# Esq.net
KiCad netlist of a schematic drawn in Altium Designer
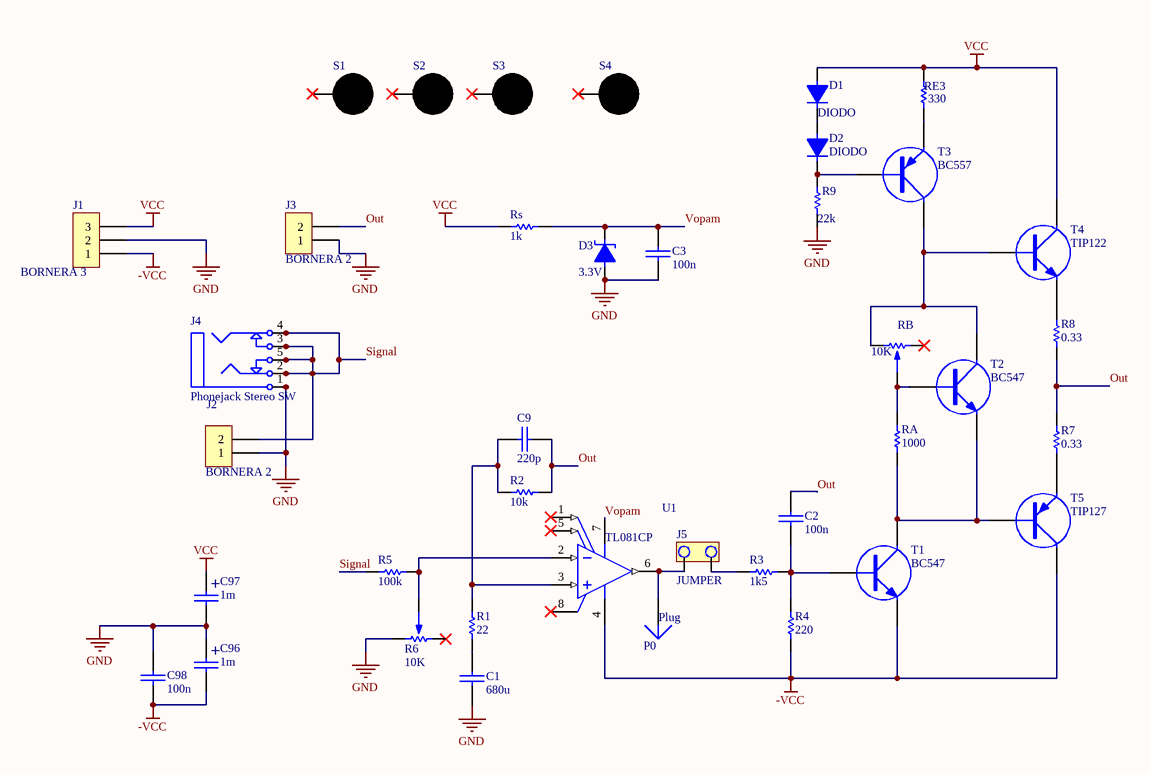
[diagram p0: Esq.SchDoc]

(export (version "E")
  (design (tool "Eeschema 10.0.6"))
  (components
    (comp (ref "C1") (value "680u") (footprint "CAP200") (libsource (lib "LIB PIO IX") (part "CAP")))
    (comp (ref "C2") (value "100n") (footprint "CAP200") (libsource (lib "LIB PIO IX") (part "CAP")))
    (comp (ref "C3") (value "100n") (footprint "CAP200") (libsource (lib "LIB PIO IX") (part "CAP")))
    (comp (ref "C9") (value "220p") (footprint "CAP200") (libsource (lib "LIB PIO IX") (part "CAP")))
    (comp (ref "C96") (value "1m") (footprint "CAP200RP2") (libsource (lib "LIB PIO IX") (part "CAPPOL")))
    (comp (ref "C97") (value "1m") (footprint "CAP200RP2") (libsource (lib "LIB PIO IX") (part "CAPPOL")))
    (comp (ref "C98") (value "100n") (footprint "CAP200") (libsource (lib "LIB PIO IX") (part "CAP")))
    (comp (ref "D1") (value "DIODO") (footprint "DO41") (libsource (lib "LIB PIO IX") (part "DIODO")))
    (comp (ref "D2") (value "DIODO") (footprint "DO41") (libsource (lib "LIB PIO IX") (part "DIODO")))
    (comp (ref "D3") (value "3.3V") (footprint "DO41") (libsource (lib "LIB PIO IX") (part "DIODO ZENER")))
    (comp (ref "J1")
      (value "BORNERA 3")
      (footprint "BORNERA3")
      (libsource (lib "LIB PIO IX") (part "BORNERA 3"))
    )
    (comp (ref "J2")
      (value "BORNERA 2")
      (footprint "BORNERA2")
      (libsource (lib "LIB PIO IX") (part "BORNERA 2"))
    )
    (comp (ref "J3")
      (value "BORNERA 2")
      (footprint "BORNERA2")
      (libsource (lib "LIB PIO IX") (part "BORNERA 2"))
    )
    (comp (ref "J4")
      (value "Phonejack Stereo SW")
      (footprint "ST-3150-5N")
      (description "3-Conductor Jack with 2 break contacts (normals) and 2 auxiliary make contacts")
      (fields (field (name "PUBLISHER") "Altium Limited"))
      (libsource (lib "Miscellaneous Connectors") (part "Phonejack Stereo SW"))
    )
    (comp (ref "J5") (value "JUMPER") (footprint "JUMPER2") (libsource (lib "LIB PIO IX") (part "JUMPER")))
    (comp (ref "P0")
      (value "Plug")
      (footprint "PIN1")
      (fields (field (name "PUBLISHER") "Altium Limited"))
      (libsource (lib "Miscellaneous Connectors") (part "Plug"))
    )
    (comp (ref "R1") (value "22") (footprint "RES400") (libsource (lib "LIB PIO IX") (part "RES")))
    (comp (ref "R2") (value "10k") (footprint "RES400") (libsource (lib "LIB PIO IX") (part "RES")))
    (comp (ref "R3") (value "1k5") (footprint "RES400") (libsource (lib "LIB PIO IX") (part "RES")))
    (comp (ref "R4") (value "220") (footprint "RES400") (libsource (lib "LIB PIO IX") (part "RES")))
    (comp (ref "R5") (value "100k") (footprint "RES400") (libsource (lib "LIB PIO IX") (part "RES")))
    (comp (ref "R6") (value "10K") (footprint "PRESET V") (libsource (lib "LIB PIO IX") (part "PRESET")))
    (comp (ref "R7") (value "0.33") (footprint "RES600") (libsource (lib "LIB PIO IX") (part "RES")))
    (comp (ref "R8") (value "0.33") (footprint "RES600") (libsource (lib "LIB PIO IX") (part "RES")))
    (comp (ref "R9") (value "22k") (footprint "RES400") (libsource (lib "LIB PIO IX") (part "RES")))
    (comp (ref "RA") (value "1000") (footprint "RES400") (libsource (lib "LIB PIO IX") (part "RES")))
    (comp (ref "RB") (value "10K") (footprint "PRESET V") (libsource (lib "LIB PIO IX") (part "PRESET")))
    (comp (ref "RE3") (value "330") (footprint "RES400") (libsource (lib "LIB PIO IX") (part "RES")))
    (comp (ref "Rs") (value "1k") (footprint "RES600") (libsource (lib "LIB PIO IX") (part "RES")))
    (comp (ref "S1")
      (value "~")
      (footprint "SUJECION (5.00MM - 3.50MM)")
      (libsource (lib "LIB2013") (part "SUJECION"))
    )
    (comp (ref "S2")
      (value "~")
      (footprint "SUJECION (5.00MM - 3.50MM)")
      (libsource (lib "LIB2013") (part "SUJECION"))
    )
    (comp (ref "S3")
      (value "~")
      (footprint "SUJECION (5.00MM - 3.50MM)")
      (libsource (lib "LIB2013") (part "SUJECION"))
    )
    (comp (ref "S4")
      (value "~")
      (footprint "SUJECION (5.00MM - 3.50MM)")
      (libsource (lib "LIB2013") (part "SUJECION"))
    )
    (comp (ref "T1")
      (value "BC547")
      (footprint "TO92")
      (libsource (lib "LIB PIO IX") (part "TRANSISTOR NPN"))
    )
    (comp (ref "T2")
      (value "BC547")
      (footprint "TO92")
      (libsource (lib "LIB PIO IX") (part "TRANSISTOR NPN"))
    )
    (comp (ref "T3")
      (value "BC557")
      (footprint "TO92")
      (libsource (lib "LIB PIO IX") (part "TRANSISTOR PNP"))
    )
    (comp (ref "T4")
      (value "TIP122")
      (footprint "TO-220 V")
      (libsource (lib "LIB PIO IX") (part "TRANSISTOR NPN"))
    )
    (comp (ref "T5")
      (value "TIP127")
      (footprint "TO-220 V")
      (libsource (lib "LIB PIO IX") (part "TRANSISTOR PNP"))
    )
    (comp (ref "U1")
      (value "TL081CP")
      (footprint "P0008A")
      (description "JFET-Input Operational Amplifier, 7 to 36 V, 0 to 70 degC, 8-pin DIP (P8), Pb-Free (RoHS)")
      (fields (field (name "MANUFACTURER") "Texas Instruments"))
      (libsource (lib "Altium Content Vault") (part "TI-AMP-S5-2-8"))
    )
  )
  (nets
    (net (code "1") (name "-VCC") (class "Default")
      (node (ref "C96") (pin "2") (pinfunction "2_2") (pintype "passive"))
      (node (ref "C98") (pin "1") (pinfunction "1_1") (pintype "passive"))
      (node (ref "J1") (pin "1") (pinfunction "1_1") (pintype "passive"))
      (node (ref "R4") (pin "1") (pinfunction "1_1") (pintype "passive"))
      (node (ref "T1") (pin "3") (pinfunction "E_3") (pintype "passive"))
      (node (ref "T5") (pin "2") (pinfunction "C_2") (pintype "passive"))
      (node (ref "U1") (pin "4") (pinfunction "VCC-_4") (pintype "power_in"))
    )
    (net (code "2") (name "/Out") (class "Default")
      (node (ref "C2") (pin "1") (pinfunction "1_1") (pintype "passive"))
      (node (ref "C9") (pin "2") (pinfunction "2_2") (pintype "passive"))
      (node (ref "J3") (pin "2") (pinfunction "2_2") (pintype "passive"))
      (node (ref "R2") (pin "2") (pinfunction "2_2") (pintype "passive"))
      (node (ref "R7") (pin "2") (pinfunction "2_2") (pintype "passive"))
      (node (ref "R8") (pin "1") (pinfunction "1_1") (pintype "passive"))
    )
    (net (code "3") (name "/Signal") (class "Default")
      (node (ref "J2") (pin "2") (pinfunction "2_2") (pintype "passive"))
      (node (ref "J4") (pin "2") (pinfunction "2_2") (pintype "passive"))
      (node (ref "J4") (pin "2A") (pinfunction "2A_2A") (pintype "passive"))
      (node (ref "J4") (pin "2B") (pinfunction "2B_2B") (pintype "passive"))
      (node (ref "J4") (pin "3") (pinfunction "3_3") (pintype "passive"))
      (node (ref "J4") (pin "3A") (pinfunction "3A_3A") (pintype "passive"))
      (node (ref "J4") (pin "3B") (pinfunction "3B_3B") (pintype "passive"))
      (node (ref "J4") (pin "4") (pinfunction "4_4") (pintype "passive"))
      (node (ref "J4") (pin "4A") (pinfunction "4A_4A") (pintype "passive"))
      (node (ref "J4") (pin "4B") (pinfunction "4B_4B") (pintype "passive"))
      (node (ref "J4") (pin "5") (pinfunction "5_5") (pintype "passive"))
      (node (ref "J4") (pin "5A") (pinfunction "5A_5A") (pintype "passive"))
      (node (ref "J4") (pin "5B") (pinfunction "5B_5B") (pintype "passive"))
      (node (ref "R5") (pin "2") (pinfunction "2_2") (pintype "passive"))
    )
    (net (code "4") (name "/Vopam") (class "Default")
      (node (ref "C3") (pin "2") (pinfunction "2_2") (pintype "passive"))
      (node (ref "D3") (pin "2") (pinfunction "2_2") (pintype "passive"))
      (node (ref "Rs") (pin "2") (pinfunction "2_2") (pintype "passive"))
      (node (ref "U1") (pin "7") (pinfunction "VCC+_7") (pintype "power_in"))
    )
    (net (code "5") (name "GND") (class "Default")
      (node (ref "C1") (pin "2") (pinfunction "2_2") (pintype "passive"))
      (node (ref "C3") (pin "1") (pinfunction "1_1") (pintype "passive"))
      (node (ref "C96") (pin "1") (pinfunction "1_1") (pintype "passive"))
      (node (ref "C97") (pin "2") (pinfunction "2_2") (pintype "passive"))
      (node (ref "C98") (pin "2") (pinfunction "2_2") (pintype "passive"))
      (node (ref "D3") (pin "1") (pinfunction "1_1") (pintype "passive"))
      (node (ref "J1") (pin "2") (pinfunction "2_2") (pintype "passive"))
      (node (ref "J2") (pin "1") (pinfunction "1_1") (pintype "passive"))
      (node (ref "J3") (pin "1") (pinfunction "1_1") (pintype "passive"))
      (node (ref "J4") (pin "1") (pinfunction "1_1") (pintype "passive"))
      (node (ref "J4") (pin "1A") (pinfunction "1A_1A") (pintype "passive"))
      (node (ref "J4") (pin "1B") (pinfunction "1B_1B") (pintype "passive"))
      (node (ref "R6") (pin "1") (pinfunction "1_1") (pintype "passive"))
      (node (ref "R9") (pin "1") (pinfunction "1_1") (pintype "passive"))
    )
    (net (code "6") (name "Net-(C1-Pad1)") (class "Default")
      (node (ref "C1") (pin "1") (pinfunction "1_1") (pintype "passive"))
      (node (ref "R1") (pin "1") (pinfunction "1_1") (pintype "passive"))
    )
    (net (code "7") (name "Net-(D1-Pad2)") (class "Default")
      (node (ref "D1") (pin "2") (pinfunction "2_2") (pintype "passive"))
      (node (ref "D2") (pin "1") (pinfunction "1_1") (pintype "passive"))
    )
    (net (code "8") (name "Net-(J5-Pad1)") (class "Default")
      (node (ref "J5") (pin "1") (pinfunction "1_1") (pintype "passive"))
      (node (ref "R3") (pin "1") (pinfunction "1_1") (pintype "passive"))
    )
    (net (code "9") (name "Net-(T1-B)") (class "Default")
      (node (ref "C2") (pin "2") (pinfunction "2_2") (pintype "passive"))
      (node (ref "R3") (pin "2") (pinfunction "2_2") (pintype "passive"))
      (node (ref "R4") (pin "2") (pinfunction "2_2") (pintype "passive"))
      (node (ref "T1") (pin "1") (pinfunction "B_1") (pintype "passive"))
    )
    (net (code "10") (name "Net-(T1-C)") (class "Default")
      (node (ref "RA") (pin "1") (pinfunction "1_1") (pintype "passive"))
      (node (ref "T1") (pin "2") (pinfunction "C_2") (pintype "passive"))
      (node (ref "T2") (pin "3") (pinfunction "E_3") (pintype "passive"))
      (node (ref "T5") (pin "1") (pinfunction "B_1") (pintype "passive"))
    )
    (net (code "11") (name "Net-(T2-B)") (class "Default")
      (node (ref "RA") (pin "2") (pinfunction "2_2") (pintype "passive"))
      (node (ref "RB") (pin "2") (pinfunction "2_2") (pintype "passive"))
      (node (ref "T2") (pin "1") (pinfunction "B_1") (pintype "passive"))
    )
    (net (code "12") (name "Net-(T2-C)") (class "Default")
      (node (ref "RB") (pin "3") (pinfunction "3_3") (pintype "passive"))
      (node (ref "T2") (pin "2") (pinfunction "C_2") (pintype "passive"))
      (node (ref "T3") (pin "2") (pinfunction "C_2") (pintype "passive"))
      (node (ref "T4") (pin "1") (pinfunction "B_1") (pintype "passive"))
    )
    (net (code "13") (name "Net-(T3-B)") (class "Default")
      (node (ref "D2") (pin "2") (pinfunction "2_2") (pintype "passive"))
      (node (ref "R9") (pin "2") (pinfunction "2_2") (pintype "passive"))
      (node (ref "T3") (pin "1") (pinfunction "B_1") (pintype "passive"))
    )
    (net (code "14") (name "Net-(T3-E)") (class "Default")
      (node (ref "RE3") (pin "1") (pinfunction "1_1") (pintype "passive"))
      (node (ref "T3") (pin "3") (pinfunction "E_3") (pintype "passive"))
    )
    (net (code "15") (name "Net-(T4-E)") (class "Default")
      (node (ref "R8") (pin "2") (pinfunction "2_2") (pintype "passive"))
      (node (ref "T4") (pin "3") (pinfunction "E_3") (pintype "passive"))
    )
    (net (code "16") (name "Net-(T5-E)") (class "Default")
      (node (ref "R7") (pin "1") (pinfunction "1_1") (pintype "passive"))
      (node (ref "T5") (pin "3") (pinfunction "E_3") (pintype "passive"))
    )
    (net (code "17") (name "Net-(U1-IN+)") (class "Default")
      (node (ref "C9") (pin "1") (pinfunction "1_1") (pintype "passive"))
      (node (ref "R1") (pin "2") (pinfunction "2_2") (pintype "passive"))
      (node (ref "R2") (pin "1") (pinfunction "1_1") (pintype "passive"))
      (node (ref "U1") (pin "3") (pinfunction "IN+_3") (pintype "input"))
    )
    (net (code "18") (name "Net-(U1-IN-)") (class "Default")
      (node (ref "R5") (pin "1") (pinfunction "1_1") (pintype "passive"))
      (node (ref "R6") (pin "2") (pinfunction "2_2") (pintype "passive"))
      (node (ref "U1") (pin "2") (pinfunction "IN-_2") (pintype "input"))
    )
    (net (code "19") (name "Net-(U1-OUT)") (class "Default")
      (node (ref "J5") (pin "2") (pinfunction "2_2") (pintype "passive"))
      (node (ref "P0") (pin "1") (pinfunction "1_1") (pintype "passive"))
      (node (ref "U1") (pin "6") (pinfunction "OUT_6") (pintype "output"))
    )
    (net (code "20") (name "VCC") (class "Default")
      (node (ref "C97") (pin "1") (pinfunction "1_1") (pintype "passive"))
      (node (ref "D1") (pin "1") (pinfunction "1_1") (pintype "passive"))
      (node (ref "J1") (pin "3") (pinfunction "3_3") (pintype "passive"))
      (node (ref "RE3") (pin "2") (pinfunction "2_2") (pintype "passive"))
      (node (ref "Rs") (pin "1") (pinfunction "1_1") (pintype "passive"))
      (node (ref "T4") (pin "2") (pinfunction "C_2") (pintype "passive"))
    )
    (net (code "21") (name "unconnected-(R6-Pad3)") (class "Default")
      (node (ref "R6") (pin "3") (pinfunction "3_3") (pintype "passive+no_connect"))
    )
    (net (code "22") (name "unconnected-(RB-Pad1)") (class "Default")
      (node (ref "RB") (pin "1") (pinfunction "1_1") (pintype "passive+no_connect"))
    )
    (net (code "23") (name "unconnected-(S1-Pad1)") (class "Default")
      (node (ref "S1") (pin "1") (pinfunction "1_1") (pintype "passive+no_connect"))
    )
    (net (code "24") (name "unconnected-(S2-Pad1)") (class "Default")
      (node (ref "S2") (pin "1") (pinfunction "1_1") (pintype "passive+no_connect"))
    )
    (net (code "25") (name "unconnected-(S3-Pad1)") (class "Default")
      (node (ref "S3") (pin "1") (pinfunction "1_1") (pintype "passive+no_connect"))
    )
    (net (code "26") (name "unconnected-(S4-Pad1)") (class "Default")
      (node (ref "S4") (pin "1") (pinfunction "1_1") (pintype "passive+no_connect"))
    )
    (net (code "27") (name "unconnected-(U1-NC-Pad8)") (class "Default")
      (node (ref "U1") (pin "8") (pinfunction "NC_8") (pintype "passive+no_connect"))
    )
    (net (code "28") (name "unconnected-(U1-OFFSET_N1-Pad1)") (class "Default")
      (node (ref "U1") (pin "1") (pinfunction "OFFSET_N1_1") (pintype "input+no_connect"))
    )
    (net (code "29") (name "unconnected-(U1-OFFSET_N2-Pad5)") (class "Default")
      (node (ref "U1") (pin "5") (pinfunction "OFFSET_N2_5") (pintype "input+no_connect"))
    )
  )
)
